# CPUBoard_p2.net
KiCad netlist of a schematic drawn in Altium Designer
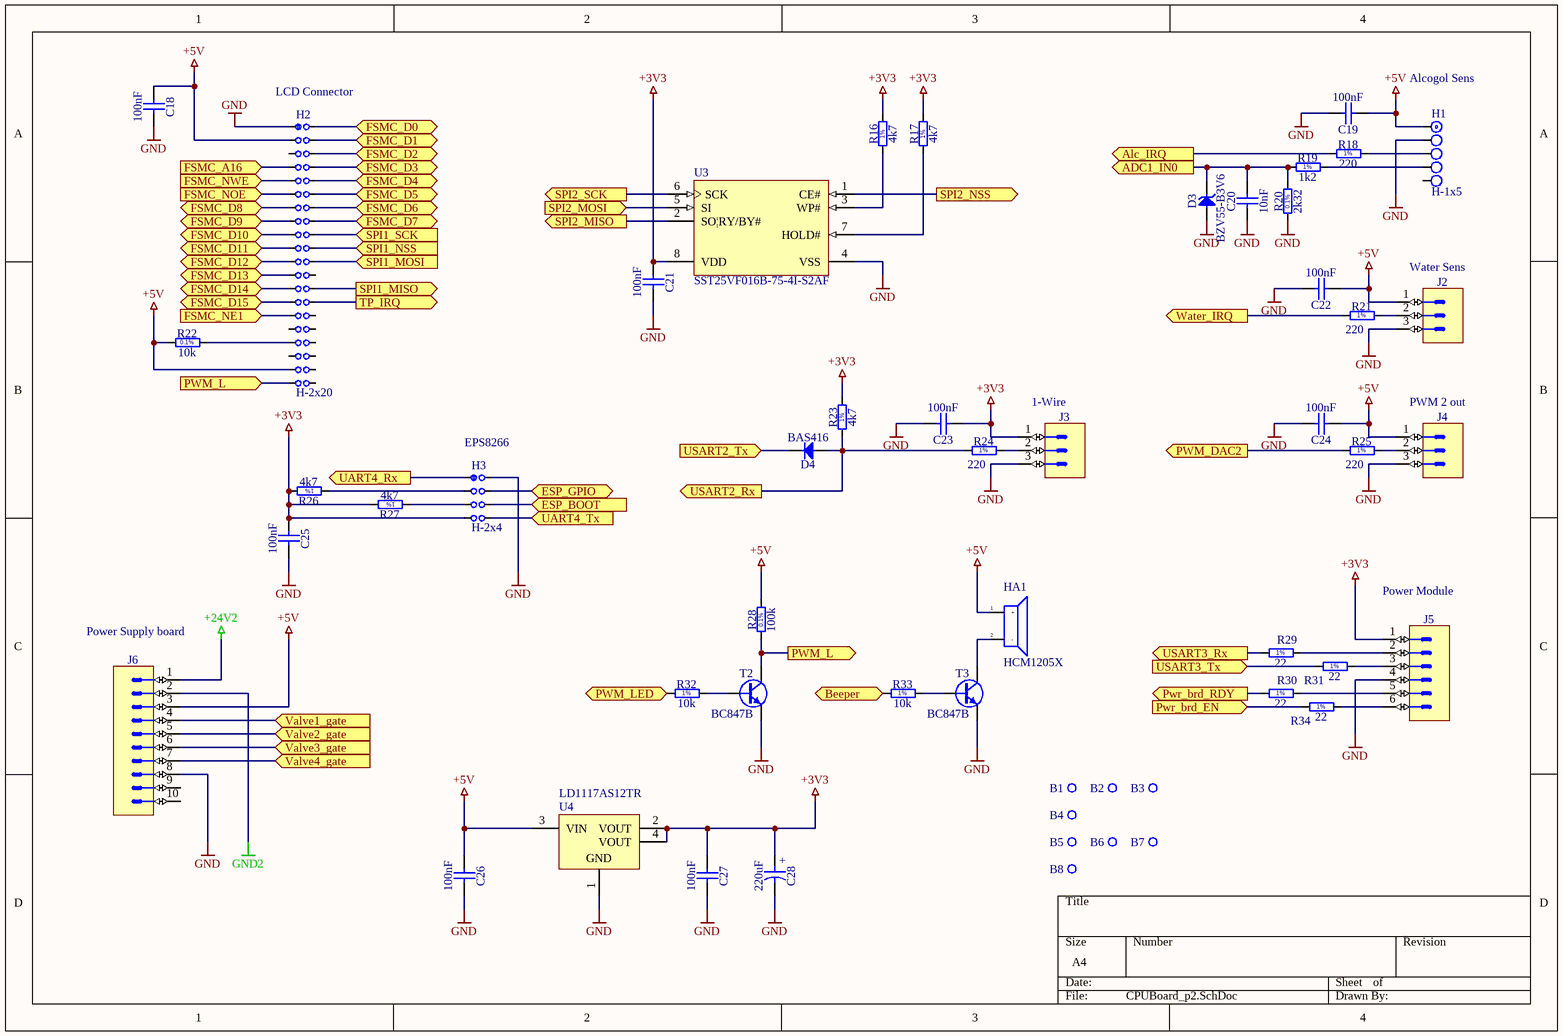
[diagram p0: CPUBoard_p2.SchDoc]

(export (version "E")
  (design (tool "Eeschema 10.0.6"))
  (components
    (comp (ref "B1")
      (value "Plated Hole")
      (footprint "MTG350_650")
      (description "Single Terminal Socket")
      (fields (field (name "PART NUMBER") "PLATED_HOLE3.5_PAD6.5") (field (name "AUTHOR") "CERN DEM JLC"))
      (libsource (lib "Eletro-mechanical") (part "Single Terminal Socket"))
    )
    (comp (ref "B2")
      (value "Plated Hole")
      (footprint "MTG350_650")
      (description "Single Terminal Socket")
      (fields (field (name "PART NUMBER") "PLATED_HOLE3.5_PAD6.5") (field (name "AUTHOR") "CERN DEM JLC"))
      (libsource (lib "Eletro-mechanical") (part "Single Terminal Socket"))
    )
    (comp (ref "B3")
      (value "Plated Hole")
      (footprint "MTG350_650")
      (description "Single Terminal Socket")
      (fields (field (name "PART NUMBER") "PLATED_HOLE3.5_PAD6.5") (field (name "AUTHOR") "CERN DEM JLC"))
      (libsource (lib "Eletro-mechanical") (part "Single Terminal Socket"))
    )
    (comp (ref "B4")
      (value "Plated Hole")
      (footprint "MTG350_650")
      (description "Single Terminal Socket")
      (fields (field (name "PART NUMBER") "PLATED_HOLE3.5_PAD6.5") (field (name "AUTHOR") "CERN DEM JLC"))
      (libsource (lib "Eletro-mechanical") (part "Single Terminal Socket"))
    )
    (comp (ref "B5")
      (value "Plated Hole")
      (footprint "MTG350_650")
      (description "Single Terminal Socket")
      (fields (field (name "PART NUMBER") "PLATED_HOLE3.5_PAD6.5") (field (name "AUTHOR") "CERN DEM JLC"))
      (libsource (lib "Eletro-mechanical") (part "Single Terminal Socket"))
    )
    (comp (ref "B6")
      (value "Plated Hole")
      (footprint "MTG350_650")
      (description "Single Terminal Socket")
      (fields (field (name "PART NUMBER") "PLATED_HOLE3.5_PAD6.5") (field (name "AUTHOR") "CERN DEM JLC"))
      (libsource (lib "Eletro-mechanical") (part "Single Terminal Socket"))
    )
    (comp (ref "B7")
      (value "Plated Hole")
      (footprint "MTG350_650")
      (description "Single Terminal Socket")
      (fields (field (name "PART NUMBER") "PLATED_HOLE3.5_PAD6.5") (field (name "AUTHOR") "CERN DEM JLC"))
      (libsource (lib "Eletro-mechanical") (part "Single Terminal Socket"))
    )
    (comp (ref "B8")
      (value "Plated Hole")
      (footprint "MTG350_650")
      (description "Single Terminal Socket")
      (fields (field (name "PART NUMBER") "PLATED_HOLE3.5_PAD6.5") (field (name "AUTHOR") "CERN DEM JLC"))
      (libsource (lib "Eletro-mechanical") (part "Single Terminal Socket"))
    )
    (comp (ref "C18")
      (value "100nF")
      (footprint "CAPC2012X135N")
      (description "Non-polarised capacitor")
      (fields
        (field (name "PART NUMBER") "CC0805_100NF_50V_10%_X7R")
        (field (name "VOLTAGE") "50V")
        (field (name "AUTHOR") "CERN DEM JLC")
      )
      (libsource (lib "Capacitors") (part "Capacitor - non polarized"))
    )
    (comp (ref "C19")
      (value "100nF")
      (footprint "CAPC2012X135N")
      (description "Non-polarised capacitor")
      (fields
        (field (name "PART NUMBER") "CC0805_100NF_50V_10%_X7R")
        (field (name "VOLTAGE") "50V")
        (field (name "AUTHOR") "CERN DEM JLC")
      )
      (libsource (lib "Capacitors") (part "Capacitor - non polarized"))
    )
    (comp (ref "C20")
      (value "10nF")
      (footprint "CAPC2012X135N")
      (description "Non-polarised capacitor")
      (fields
        (field (name "PART NUMBER") "CC0805_10NF_50V_5%_X7R")
        (field (name "VOLTAGE") "50V")
        (field (name "AUTHOR") "CERN DEM JLC")
      )
      (libsource (lib "Capacitors") (part "Capacitor - non polarized"))
    )
    (comp (ref "C21")
      (value "100nF")
      (footprint "CAPC2012X135N")
      (description "Non-polarised capacitor")
      (fields
        (field (name "PART NUMBER") "CC0805_100NF_50V_10%_X7R")
        (field (name "VOLTAGE") "50V")
        (field (name "AUTHOR") "CERN DEM JLC")
      )
      (libsource (lib "Capacitors") (part "Capacitor - non polarized"))
    )
    (comp (ref "C22")
      (value "100nF")
      (footprint "CAPC2012X135N")
      (description "Non-polarised capacitor")
      (fields
        (field (name "PART NUMBER") "CC0805_100NF_50V_10%_X7R")
        (field (name "VOLTAGE") "50V")
        (field (name "AUTHOR") "CERN DEM JLC")
      )
      (libsource (lib "Capacitors") (part "Capacitor - non polarized"))
    )
    (comp (ref "C23")
      (value "100nF")
      (footprint "CAPC2012X135N")
      (description "Non-polarised capacitor")
      (fields
        (field (name "PART NUMBER") "CC0805_100NF_50V_10%_X7R")
        (field (name "VOLTAGE") "50V")
        (field (name "AUTHOR") "CERN DEM JLC")
      )
      (libsource (lib "Capacitors") (part "Capacitor - non polarized"))
    )
    (comp (ref "C24")
      (value "100nF")
      (footprint "CAPC2012X135N")
      (description "Non-polarised capacitor")
      (fields
        (field (name "PART NUMBER") "CC0805_100NF_50V_10%_X7R")
        (field (name "VOLTAGE") "50V")
        (field (name "AUTHOR") "CERN DEM JLC")
      )
      (libsource (lib "Capacitors") (part "Capacitor - non polarized"))
    )
    (comp (ref "C25")
      (value "100nF")
      (footprint "CAPC2012X135N")
      (description "Non-polarised capacitor")
      (fields
        (field (name "PART NUMBER") "CC0805_100NF_50V_10%_X7R")
        (field (name "VOLTAGE") "50V")
        (field (name "AUTHOR") "CERN DEM JLC")
      )
      (libsource (lib "Capacitors") (part "Capacitor - non polarized"))
    )
    (comp (ref "C26")
      (value "100nF")
      (footprint "CAPC2012X135N")
      (description "Non-polarised capacitor")
      (fields
        (field (name "PART NUMBER") "CC0805_100NF_50V_10%_X7R")
        (field (name "VOLTAGE") "50V")
        (field (name "AUTHOR") "CERN DEM JLC")
      )
      (libsource (lib "Capacitors") (part "Capacitor - non polarized"))
    )
    (comp (ref "C27")
      (value "100nF")
      (footprint "CAPC2012X135N")
      (description "Non-polarised capacitor")
      (fields
        (field (name "PART NUMBER") "CC0805_100NF_50V_10%_X7R")
        (field (name "VOLTAGE") "50V")
        (field (name "AUTHOR") "CERN DEM JLC")
      )
      (libsource (lib "Capacitors") (part "Capacitor - non polarized"))
    )
    (comp (ref "C28")
      (value "220uF")
      (footprint "CAPPR350-850X1300")
      (description "Polarised capacitor")
      (fields
        (field (name "PART NUMBER") "CAER_220UF_25V_20%_RUBYCON_25YXF220M8X11.5")
        (field (name "VOLTAGE") "25V")
        (field (name "AUTHOR") "CERN DEM JLC")
      )
      (libsource (lib "Capacitors") (part "Capacitor - polarized"))
    )
    (comp (ref "D3")
      (value "BZV55-B3V6")
      (footprint "DIOMELF3515N")
      (description "Zener Diode")
      (fields
        (field (name "VOLTAGE") "3V6")
        (field (name "POWER") "500mW")
        (field (name "AUTHOR") "CERN DEM JLC")
      )
      (libsource (lib "ICs And Semiconductors") (part "Diode Zener"))
    )
    (comp (ref "D4")
      (value "BAS416")
      (footprint "SOD2512X110N")
      (description "Diode")
      (fields
        (field (name "VOLTAGE") "75V")
        (field (name "POWER") "200mA")
        (field (name "AUTHOR") "CERN DEM JLC")
      )
      (libsource (lib "ICs And Semiconductors") (part "Diode"))
    )
    (comp (ref "H1") (value "H-1x5") (footprint "J1x5") (libsource (lib "Connektor") (part "H-1x5")))
    (comp (ref "H2") (value "H-2x20") (footprint "J2x20") (libsource (lib "Connektor") (part "H-2x20")))
    (comp (ref "H3") (value "H-2x4") (footprint "J2x4") (libsource (lib "Connektor") (part "H-2x4")))
    (comp (ref "HA1")
      (value "HCM1205X")
      (footprint "HCM1205X")
      (libsource (lib "PowerLib") (part "HCM1205X"))
    )
    (comp (ref "J2")
      (value "KK®")
      (footprint "MOLEX_22-04-1031")
      (description "Connector 3 Male")
      (fields
        (field (name "PART NUMBER") "MOLEX_22-04-1031")
        (field (name "MANUFACTURER") "MOLEX")
        (field (name "AUTHOR") "CERN DEM JLC")
      )
      (libsource (lib "Connectors") (part "Connector 3 Male"))
    )
    (comp (ref "J3")
      (value "KK®")
      (footprint "MOLEX_22-04-1031")
      (description "Connector 3 Male")
      (fields
        (field (name "PART NUMBER") "MOLEX_22-04-1031")
        (field (name "MANUFACTURER") "MOLEX")
        (field (name "AUTHOR") "CERN DEM JLC")
      )
      (libsource (lib "Connectors") (part "Connector 3 Male"))
    )
    (comp (ref "J4")
      (value "KK®")
      (footprint "MOLEX_22-04-1031")
      (description "Connector 3 Male")
      (fields
        (field (name "PART NUMBER") "MOLEX_22-04-1031")
        (field (name "MANUFACTURER") "MOLEX")
        (field (name "AUTHOR") "CERN DEM JLC")
      )
      (libsource (lib "Connectors") (part "Connector 3 Male"))
    )
    (comp (ref "J5")
      (value "KK®")
      (footprint "MOLEX_22-27-2061")
      (description "Connector 6 Male")
      (fields
        (field (name "PART NUMBER") "MOLEX_22-27-2061")
        (field (name "MANUFACTURER") "MOLEX")
        (field (name "AUTHOR") "CERN DEM JMW")
      )
      (libsource (lib "Connectors") (part "Connector 6 Male"))
    )
    (comp (ref "J6")
      (value "C-Grid®")
      (footprint "MOLEX_70246-1004")
      (description "Connector 10 Male")
      (fields
        (field (name "PART NUMBER") "MOLEX_70246-1004")
        (field (name "MANUFACTURER") "MOLEX")
        (field (name "AUTHOR") "CERN DEM JLC")
      )
      (libsource (lib "Connectors") (part "Connector 10 Male"))
    )
    (comp (ref "R16")
      (value "4k7")
      (footprint "RESC2012X60N")
      (description "Resistor - 1%")
      (fields
        (field (name "PART NUMBER") "R0805_4K7_1%_0.125W_100PPM")
        (field (name "POWER") "0.125W")
        (field (name "AUTHOR") "CERN DEM JLC")
      )
      (libsource (lib "Resistors") (part "Resistor - 1%"))
    )
    (comp (ref "R17")
      (value "4k7")
      (footprint "RESC2012X60N")
      (description "Resistor - 1%")
      (fields
        (field (name "PART NUMBER") "R0805_4K7_1%_0.125W_100PPM")
        (field (name "POWER") "0.125W")
        (field (name "AUTHOR") "CERN DEM JLC")
      )
      (libsource (lib "Resistors") (part "Resistor - 1%"))
    )
    (comp (ref "R18")
      (value "220")
      (footprint "RESC2012X60N")
      (description "Resistor - 1%")
      (fields
        (field (name "PART NUMBER") "R0805_220R_1%_0.125W_100PPM")
        (field (name "POWER") "0.125W")
        (field (name "AUTHOR") "CERN DEM JLC")
      )
      (libsource (lib "Resistors") (part "Resistor - 1%"))
    )
    (comp (ref "R19")
      (value "1k2")
      (footprint "RESC2012X60N")
      (description "Resistor - 1%")
      (fields
        (field (name "PART NUMBER") "R0805_1K2_1%_0.125W_100PPM")
        (field (name "POWER") "0.125W")
        (field (name "AUTHOR") "CERN DEM JLC")
      )
      (libsource (lib "Resistors") (part "Resistor - 1%"))
    )
    (comp (ref "R20")
      (value "2k32")
      (footprint "RESC2012X60N")
      (description "Resistor - 0.1%")
      (fields
        (field (name "PART NUMBER") "R0805_2K32_0.1%_0.1W_10PPM")
        (field (name "POWER") "0.1W")
        (field (name "AUTHOR") "CERN DEM JLC")
      )
      (libsource (lib "Resistors") (part "Resistor - 0.1%"))
    )
    (comp (ref "R21")
      (value "220")
      (footprint "RESC2012X60N")
      (description "Resistor - 1%")
      (fields
        (field (name "PART NUMBER") "R0805_220R_1%_0.125W_100PPM")
        (field (name "POWER") "0.125W")
        (field (name "AUTHOR") "CERN DEM JLC")
      )
      (libsource (lib "Resistors") (part "Resistor - 1%"))
    )
    (comp (ref "R22")
      (value "10k")
      (footprint "RESC2012X60N")
      (description "Resistor - 0.1%")
      (fields
        (field (name "PART NUMBER") "R0805_10K_0.1%_0.1W_10PPM")
        (field (name "POWER") "0.1W")
        (field (name "AUTHOR") "CERN DEM JLC")
      )
      (libsource (lib "Resistors") (part "Resistor - 0.1%"))
    )
    (comp (ref "R23")
      (value "4k7")
      (footprint "RESC2012X60N")
      (description "Resistor - 1%")
      (fields
        (field (name "PART NUMBER") "R0805_4K7_1%_0.125W_100PPM")
        (field (name "POWER") "0.125W")
        (field (name "AUTHOR") "CERN DEM JLC")
      )
      (libsource (lib "Resistors") (part "Resistor - 1%"))
    )
    (comp (ref "R24")
      (value "220")
      (footprint "RESC2012X60N")
      (description "Resistor - 1%")
      (fields
        (field (name "PART NUMBER") "R0805_220R_1%_0.125W_100PPM")
        (field (name "POWER") "0.125W")
        (field (name "AUTHOR") "CERN DEM JLC")
      )
      (libsource (lib "Resistors") (part "Resistor - 1%"))
    )
    (comp (ref "R25")
      (value "220")
      (footprint "RESC2012X60N")
      (description "Resistor - 1%")
      (fields
        (field (name "PART NUMBER") "R0805_220R_1%_0.125W_100PPM")
        (field (name "POWER") "0.125W")
        (field (name "AUTHOR") "CERN DEM JLC")
      )
      (libsource (lib "Resistors") (part "Resistor - 1%"))
    )
    (comp (ref "R26")
      (value "4k7")
      (footprint "RESC2012X60N")
      (description "Resistor - 1%")
      (fields
        (field (name "PART NUMBER") "R0805_4K7_1%_0.125W_100PPM")
        (field (name "POWER") "0.125W")
        (field (name "AUTHOR") "CERN DEM JLC")
      )
      (libsource (lib "Resistors") (part "Resistor - 1%"))
    )
    (comp (ref "R27")
      (value "4k7")
      (footprint "RESC2012X60N")
      (description "Resistor - 1%")
      (fields
        (field (name "PART NUMBER") "R0805_4K7_1%_0.125W_100PPM")
        (field (name "POWER") "0.125W")
        (field (name "AUTHOR") "CERN DEM JLC")
      )
      (libsource (lib "Resistors") (part "Resistor - 1%"))
    )
    (comp (ref "R28")
      (value "100k")
      (footprint "RESC2012X60N")
      (description "Resistor - 0.1%")
      (fields
        (field (name "PART NUMBER") "R0805_100K_0.1%_0.1W_10PPM")
        (field (name "POWER") "0.1W")
        (field (name "AUTHOR") "CERN DEM JLC")
      )
      (libsource (lib "Resistors") (part "Resistor - 0.1%"))
    )
    (comp (ref "R29")
      (value "22")
      (footprint "RESC2012X60N")
      (description "Resistor - 1%")
      (fields
        (field (name "PART NUMBER") "R0805_22R_1%_0.125W_100PPM")
        (field (name "POWER") "0.125W")
        (field (name "AUTHOR") "CERN DEM JLC")
      )
      (libsource (lib "Resistors") (part "Resistor - 1%"))
    )
    (comp (ref "R30")
      (value "22")
      (footprint "RESC2012X60N")
      (description "Resistor - 1%")
      (fields
        (field (name "PART NUMBER") "R0805_22R_1%_0.125W_100PPM")
        (field (name "POWER") "0.125W")
        (field (name "AUTHOR") "CERN DEM JLC")
      )
      (libsource (lib "Resistors") (part "Resistor - 1%"))
    )
    (comp (ref "R31")
      (value "22")
      (footprint "RESC2012X60N")
      (description "Resistor - 1%")
      (fields
        (field (name "PART NUMBER") "R0805_22R_1%_0.125W_100PPM")
        (field (name "POWER") "0.125W")
        (field (name "AUTHOR") "CERN DEM JLC")
      )
      (libsource (lib "Resistors") (part "Resistor - 1%"))
    )
    (comp (ref "R32")
      (value "10k")
      (footprint "RESC2012X60N")
      (description "Resistor - 1%")
      (fields
        (field (name "PART NUMBER") "R0805_10K_1%_0.125W_100PPM")
        (field (name "POWER") "0.125W")
        (field (name "AUTHOR") "CERN DEM JLC")
      )
      (libsource (lib "Resistors") (part "Resistor - 1%"))
    )
    (comp (ref "R33")
      (value "10k")
      (footprint "RESC2012X60N")
      (description "Resistor - 1%")
      (fields
        (field (name "PART NUMBER") "R0805_10K_1%_0.125W_100PPM")
        (field (name "POWER") "0.125W")
        (field (name "AUTHOR") "CERN DEM JLC")
      )
      (libsource (lib "Resistors") (part "Resistor - 1%"))
    )
    (comp (ref "R34")
      (value "22")
      (footprint "RESC2012X60N")
      (description "Resistor - 1%")
      (fields
        (field (name "PART NUMBER") "R0805_22R_1%_0.125W_100PPM")
        (field (name "POWER") "0.125W")
        (field (name "AUTHOR") "CERN DEM JLC")
      )
      (libsource (lib "Resistors") (part "Resistor - 1%"))
    )
    (comp (ref "T2")
      (value "BC847B")
      (footprint "SOT95P230X110-3N")
      (description "NPN Transistor")
      (fields (field (name "MANUFACTURER") "NXP SEMICONDUCTORS") (field (name "AUTHOR") "CERN DEM JLC"))
      (libsource (lib "ICs And Semiconductors") (part "NPN B1 E2 C3"))
    )
    (comp (ref "T3")
      (value "BC847B")
      (footprint "SOT95P230X110-3N")
      (description "NPN Transistor")
      (fields (field (name "MANUFACTURER") "NXP SEMICONDUCTORS") (field (name "AUTHOR") "CERN DEM JLC"))
      (libsource (lib "ICs And Semiconductors") (part "NPN B1 E2 C3"))
    )
    (comp (ref "U3")
      (value "SST25VF016B-75-4I-S2AF")
      (footprint "MCHP-SOIC-S2A8_N")
      (description "16 Mbit SPI Serial Flash, 2.7 to 3.6 V, 80 MHz, -40 to 85 degC, 8-pin SOIC (S2A8), Tube")
      (fields (field (name "MANUFACTURER") "Microchip"))
      (libsource (lib "Microchip SST Flash") (part "SST25VF016B-75-4I-S2AF"))
    )
    (comp (ref "U4")
      (value "LD1117AS12TR")
      (footprint "SOT-223_N")
      (description "1A, Low Drop Positive Voltage Regulator, 1.2V, 4-Pin SOT-223, Tape and Reel")
      (libsource (lib "STMicroelectronics Power Management Linear Regulator") (part "LD1117AS12TR"))
    )
  )
  (nets
    (net (code "1") (name "+3V3") (class "Default")
      (node (ref "C21") (pin "1") (pinfunction "1_1") (pintype "passive"))
      (node (ref "C23") (pin "1") (pinfunction "1_1") (pintype "passive"))
      (node (ref "C25") (pin "1") (pinfunction "1_1") (pintype "passive"))
      (node (ref "C27") (pin "1") (pinfunction "1_1") (pintype "passive"))
      (node (ref "C28") (pin "1") (pinfunction "1_1") (pintype "passive"))
      (node (ref "H3") (pin "7") (pinfunction "7_7") (pintype "passive"))
      (node (ref "J3") (pin "1") (pinfunction "1_1") (pintype "bidirectional"))
      (node (ref "J5") (pin "1") (pinfunction "1_1") (pintype "bidirectional"))
      (node (ref "R16") (pin "2") (pinfunction "2_2") (pintype "passive"))
      (node (ref "R17") (pin "2") (pinfunction "2_2") (pintype "passive"))
      (node (ref "R23") (pin "2") (pinfunction "2_2") (pintype "passive"))
      (node (ref "R26") (pin "2") (pinfunction "2_2") (pintype "passive"))
      (node (ref "R27") (pin "2") (pinfunction "2_2") (pintype "passive"))
      (node (ref "U3") (pin "8") (pinfunction "VDD_8") (pintype "power_in"))
      (node (ref "U4") (pin "2") (pinfunction "VOUT_2") (pintype "power_in"))
      (node (ref "U4") (pin "4") (pinfunction "VOUT_4") (pintype "power_in"))
    )
    (net (code "2") (name "+5V") (class "Default")
      (node (ref "C18") (pin "1") (pinfunction "1_1") (pintype "passive"))
      (node (ref "C19") (pin "1") (pinfunction "1_1") (pintype "passive"))
      (node (ref "C22") (pin "1") (pinfunction "1_1") (pintype "passive"))
      (node (ref "C24") (pin "1") (pinfunction "1_1") (pintype "passive"))
      (node (ref "C26") (pin "1") (pinfunction "1_1") (pintype "passive"))
      (node (ref "H1") (pin "1") (pinfunction "1_1") (pintype "passive"))
      (node (ref "H2") (pin "3") (pinfunction "3_3") (pintype "passive"))
      (node (ref "H2") (pin "37") (pinfunction "37_37") (pintype "passive"))
      (node (ref "HA1") (pin "1") (pinfunction "+_1") (pintype "passive"))
      (node (ref "J2") (pin "1") (pinfunction "1_1") (pintype "bidirectional"))
      (node (ref "J4") (pin "1") (pinfunction "1_1") (pintype "bidirectional"))
      (node (ref "J6") (pin "3") (pinfunction "3_3") (pintype "bidirectional"))
      (node (ref "R22") (pin "1") (pinfunction "1_1") (pintype "passive"))
      (node (ref "R28") (pin "2") (pinfunction "2_2") (pintype "passive"))
      (node (ref "U4") (pin "3") (pinfunction "VIN_3") (pintype "power_in"))
    )
    (net (code "3") (name "+24V2") (class "Default")
      (node (ref "J6") (pin "1") (pinfunction "1_1") (pintype "bidirectional"))
    )
    (net (code "4") (name "/ADC1_IN0") (class "Default")
      (node (ref "C20") (pin "2") (pinfunction "2_2") (pintype "passive"))
      (node (ref "D3") (pin "1") (pinfunction "C_1") (pintype "passive"))
      (node (ref "R19") (pin "1") (pinfunction "1_1") (pintype "passive"))
      (node (ref "R20") (pin "2") (pinfunction "2_2") (pintype "passive"))
    )
    (net (code "5") (name "/Alc_IRQ") (class "Default")
      (node (ref "R18") (pin "1") (pinfunction "1_1") (pintype "passive"))
    )
    (net (code "6") (name "/Beeper") (class "Default")
      (node (ref "R33") (pin "1") (pinfunction "1_1") (pintype "passive"))
    )
    (net (code "7") (name "/ESP_BOOT") (class "Default")
      (node (ref "H3") (pin "6") (pinfunction "6_6") (pintype "passive"))
    )
    (net (code "8") (name "/ESP_GPIO") (class "Default")
      (node (ref "H3") (pin "4") (pinfunction "4_4") (pintype "passive"))
    )
    (net (code "9") (name "/FSMC_A16") (class "Default")
      (node (ref "H2") (pin "7") (pinfunction "7_7") (pintype "passive"))
    )
    (net (code "10") (name "/FSMC_D0") (class "Default")
      (node (ref "H2") (pin "2") (pinfunction "2_2") (pintype "passive"))
    )
    (net (code "11") (name "/FSMC_D1") (class "Default")
      (node (ref "H2") (pin "4") (pinfunction "4_4") (pintype "passive"))
    )
    (net (code "12") (name "/FSMC_D2") (class "Default")
      (node (ref "H2") (pin "6") (pinfunction "6_6") (pintype "passive"))
    )
    (net (code "13") (name "/FSMC_D3") (class "Default")
      (node (ref "H2") (pin "8") (pinfunction "8_8") (pintype "passive"))
    )
    (net (code "14") (name "/FSMC_D4") (class "Default")
      (node (ref "H2") (pin "10") (pinfunction "10_10") (pintype "passive"))
    )
    (net (code "15") (name "/FSMC_D5") (class "Default")
      (node (ref "H2") (pin "12") (pinfunction "12_12") (pintype "passive"))
    )
    (net (code "16") (name "/FSMC_D6") (class "Default")
      (node (ref "H2") (pin "14") (pinfunction "14_14") (pintype "passive"))
    )
    (net (code "17") (name "/FSMC_D7") (class "Default")
      (node (ref "H2") (pin "16") (pinfunction "16_16") (pintype "passive"))
    )
    (net (code "18") (name "/FSMC_D8") (class "Default")
      (node (ref "H2") (pin "13") (pinfunction "13_13") (pintype "passive"))
    )
    (net (code "19") (name "/FSMC_D9") (class "Default")
      (node (ref "H2") (pin "15") (pinfunction "15_15") (pintype "passive"))
    )
    (net (code "20") (name "/FSMC_D10") (class "Default")
      (node (ref "H2") (pin "17") (pinfunction "17_17") (pintype "passive"))
    )
    (net (code "21") (name "/FSMC_D11") (class "Default")
      (node (ref "H2") (pin "19") (pinfunction "19_19") (pintype "passive"))
    )
    (net (code "22") (name "/FSMC_D12") (class "Default")
      (node (ref "H2") (pin "21") (pinfunction "21_21") (pintype "passive"))
    )
    (net (code "23") (name "/FSMC_D13") (class "Default")
      (node (ref "H2") (pin "23") (pinfunction "23_23") (pintype "passive"))
    )
    (net (code "24") (name "/FSMC_D14") (class "Default")
      (node (ref "H2") (pin "25") (pinfunction "25_25") (pintype "passive"))
    )
    (net (code "25") (name "/FSMC_D15") (class "Default")
      (node (ref "H2") (pin "27") (pinfunction "27_27") (pintype "passive"))
    )
    (net (code "26") (name "/FSMC_NE1") (class "Default")
      (node (ref "H2") (pin "29") (pinfunction "29_29") (pintype "passive"))
    )
    (net (code "27") (name "/FSMC_NOE") (class "Default")
      (node (ref "H2") (pin "11") (pinfunction "11_11") (pintype "passive"))
    )
    (net (code "28") (name "/FSMC_NWE") (class "Default")
      (node (ref "H2") (pin "9") (pinfunction "9_9") (pintype "passive"))
    )
    (net (code "29") (name "/PWM_DAC2") (class "Default")
      (node (ref "R25") (pin "1") (pinfunction "1_1") (pintype "passive"))
    )
    (net (code "30") (name "/PWM_L") (class "Default")
      (node (ref "H2") (pin "39") (pinfunction "39_39") (pintype "passive"))
      (node (ref "R28") (pin "1") (pinfunction "1_1") (pintype "passive"))
      (node (ref "T2") (pin "3") (pinfunction "C_3") (pintype "passive"))
    )
    (net (code "31") (name "/PWM_LED") (class "Default")
      (node (ref "R32") (pin "1") (pinfunction "1_1") (pintype "passive"))
    )
    (net (code "32") (name "/Pwr_brd_EN") (class "Default")
      (node (ref "R34") (pin "1") (pinfunction "1_1") (pintype "passive"))
    )
    (net (code "33") (name "/Pwr_brd_RDY") (class "Default")
      (node (ref "R30") (pin "1") (pinfunction "1_1") (pintype "passive"))
    )
    (net (code "34") (name "/SPI1_MISO") (class "Default")
      (node (ref "H2") (pin "26") (pinfunction "26_26") (pintype "passive"))
    )
    (net (code "35") (name "/SPI1_MOSI") (class "Default")
      (node (ref "H2") (pin "22") (pinfunction "22_22") (pintype "passive"))
    )
    (net (code "36") (name "/SPI1_NSS") (class "Default")
      (node (ref "H2") (pin "20") (pinfunction "20_20") (pintype "passive"))
    )
    (net (code "37") (name "/SPI1_SCK") (class "Default")
      (node (ref "H2") (pin "18") (pinfunction "18_18") (pintype "passive"))
    )
    (net (code "38") (name "/SPI2_MISO") (class "Default")
      (node (ref "U3") (pin "2") (pinfunction "SO¦RY/BY#_2") (pintype "tri_state"))
    )
    (net (code "39") (name "/SPI2_MOSI") (class "Default")
      (node (ref "U3") (pin "5") (pinfunction "SI_5") (pintype "input"))
    )
    (net (code "40") (name "/SPI2_NSS") (class "Default")
      (node (ref "U3") (pin "1") (pinfunction "CE#_1") (pintype "input"))
    )
    (net (code "41") (name "/SPI2_SCK") (class "Default")
      (node (ref "U3") (pin "6") (pinfunction "SCK_6") (pintype "input"))
    )
    (net (code "42") (name "/TP_IRQ") (class "Default")
      (node (ref "H2") (pin "28") (pinfunction "28_28") (pintype "passive"))
    )
    (net (code "43") (name "/UART4_Rx") (class "Default")
      (node (ref "H3") (pin "1") (pinfunction "1_1") (pintype "passive"))
    )
    (net (code "44") (name "/UART4_Tx") (class "Default")
      (node (ref "H3") (pin "8") (pinfunction "8_8") (pintype "passive"))
    )
    (net (code "45") (name "/USART2_Rx") (class "Default")
      (node (ref "D4") (pin "2") (pinfunction "A_2") (pintype "passive"))
      (node (ref "R23") (pin "1") (pinfunction "1_1") (pintype "passive"))
      (node (ref "R24") (pin "1") (pinfunction "1_1") (pintype "passive"))
    )
    (net (code "46") (name "/USART2_Tx") (class "Default")
      (node (ref "D4") (pin "1") (pinfunction "C_1") (pintype "passive"))
    )
    (net (code "47") (name "/USART3_Rx") (class "Default")
      (node (ref "R29") (pin "1") (pinfunction "1_1") (pintype "passive"))
    )
    (net (code "48") (name "/USART3_Tx") (class "Default")
      (node (ref "R31") (pin "1") (pinfunction "1_1") (pintype "passive"))
    )
    (net (code "49") (name "/Valve1_gate") (class "Default")
      (node (ref "J6") (pin "4") (pinfunction "4_4") (pintype "bidirectional"))
    )
    (net (code "50") (name "/Valve2_gate") (class "Default")
      (node (ref "J6") (pin "5") (pinfunction "5_5") (pintype "bidirectional"))
    )
    (net (code "51") (name "/Valve3_gate") (class "Default")
      (node (ref "J6") (pin "6") (pinfunction "6_6") (pintype "bidirectional"))
    )
    (net (code "52") (name "/Valve4_gate") (class "Default")
      (node (ref "J6") (pin "7") (pinfunction "7_7") (pintype "bidirectional"))
    )
    (net (code "53") (name "/Water_IRQ") (class "Default")
      (node (ref "R21") (pin "1") (pinfunction "1_1") (pintype "passive"))
    )
    (net (code "54") (name "GND") (class "Default")
      (node (ref "C18") (pin "2") (pinfunction "2_2") (pintype "passive"))
      (node (ref "C19") (pin "2") (pinfunction "2_2") (pintype "passive"))
      (node (ref "C20") (pin "1") (pinfunction "1_1") (pintype "passive"))
      (node (ref "C21") (pin "2") (pinfunction "2_2") (pintype "passive"))
      (node (ref "C22") (pin "2") (pinfunction "2_2") (pintype "passive"))
      (node (ref "C23") (pin "2") (pinfunction "2_2") (pintype "passive"))
      (node (ref "C24") (pin "2") (pinfunction "2_2") (pintype "passive"))
      (node (ref "C25") (pin "2") (pinfunction "2_2") (pintype "passive"))
      (node (ref "C26") (pin "2") (pinfunction "2_2") (pintype "passive"))
      (node (ref "C27") (pin "2") (pinfunction "2_2") (pintype "passive"))
      (node (ref "C28") (pin "2") (pinfunction "2_2") (pintype "passive"))
      (node (ref "D3") (pin "2") (pinfunction "A_2") (pintype "passive"))
      (node (ref "H1") (pin "2") (pinfunction "2_2") (pintype "passive"))
      (node (ref "H2") (pin "1") (pinfunction "1_1") (pintype "passive"))
      (node (ref "H3") (pin "2") (pinfunction "2_2") (pintype "passive"))
      (node (ref "J2") (pin "3") (pinfunction "3_3") (pintype "bidirectional"))
      (node (ref "J3") (pin "3") (pinfunction "3_3") (pintype "bidirectional"))
      (node (ref "J4") (pin "3") (pinfunction "3_3") (pintype "bidirectional"))
      (node (ref "J5") (pin "4") (pinfunction "4_4") (pintype "bidirectional"))
      (node (ref "J6") (pin "8") (pinfunction "8_8") (pintype "bidirectional"))
      (node (ref "R20") (pin "1") (pinfunction "1_1") (pintype "passive"))
      (node (ref "T2") (pin "2") (pinfunction "E_2") (pintype "passive"))
      (node (ref "T3") (pin "2") (pinfunction "E_2") (pintype "passive"))
      (node (ref "U3") (pin "4") (pinfunction "VSS_4") (pintype "power_in"))
      (node (ref "U4") (pin "1") (pinfunction "GND_1") (pintype "power_in"))
    )
    (net (code "55") (name "GND2") (class "Default")
      (node (ref "J6") (pin "2") (pinfunction "2_2") (pintype "bidirectional"))
    )
    (net (code "56") (name "Net-(H1-Pad3)") (class "Default")
      (node (ref "H1") (pin "3") (pinfunction "3_3") (pintype "passive"))
      (node (ref "R18") (pin "2") (pinfunction "2_2") (pintype "passive"))
    )
    (net (code "57") (name "Net-(H1-Pad4)") (class "Default")
      (node (ref "H1") (pin "4") (pinfunction "4_4") (pintype "passive"))
      (node (ref "R19") (pin "2") (pinfunction "2_2") (pintype "passive"))
    )
    (net (code "58") (name "Net-(H2-Pad33)") (class "Default")
      (node (ref "H2") (pin "33") (pinfunction "33_33") (pintype "passive"))
      (node (ref "R22") (pin "2") (pinfunction "2_2") (pintype "passive"))
    )
    (net (code "59") (name "Net-(H3-Pad3)") (class "Default")
      (node (ref "H3") (pin "3") (pinfunction "3_3") (pintype "passive"))
      (node (ref "R26") (pin "1") (pinfunction "1_1") (pintype "passive"))
    )
    (net (code "60") (name "Net-(H3-Pad5)") (class "Default")
      (node (ref "H3") (pin "5") (pinfunction "5_5") (pintype "passive"))
      (node (ref "R27") (pin "1") (pinfunction "1_1") (pintype "passive"))
    )
    (net (code "61") (name "Net-(HA1--)") (class "Default")
      (node (ref "HA1") (pin "2") (pinfunction "-_2") (pintype "passive"))
      (node (ref "T3") (pin "3") (pinfunction "C_3") (pintype "passive"))
    )
    (net (code "62") (name "Net-(J2-Pad2)") (class "Default")
      (node (ref "J2") (pin "2") (pinfunction "2_2") (pintype "bidirectional"))
      (node (ref "R21") (pin "2") (pinfunction "2_2") (pintype "passive"))
    )
    (net (code "63") (name "Net-(J3-Pad2)") (class "Default")
      (node (ref "J3") (pin "2") (pinfunction "2_2") (pintype "bidirectional"))
      (node (ref "R24") (pin "2") (pinfunction "2_2") (pintype "passive"))
    )
    (net (code "64") (name "Net-(J4-Pad2)") (class "Default")
      (node (ref "J4") (pin "2") (pinfunction "2_2") (pintype "bidirectional"))
      (node (ref "R25") (pin "2") (pinfunction "2_2") (pintype "passive"))
    )
    (net (code "65") (name "Net-(J5-Pad2)") (class "Default")
      (node (ref "J5") (pin "2") (pinfunction "2_2") (pintype "bidirectional"))
      (node (ref "R29") (pin "2") (pinfunction "2_2") (pintype "passive"))
    )
    (net (code "66") (name "Net-(J5-Pad3)") (class "Default")
      (node (ref "J5") (pin "3") (pinfunction "3_3") (pintype "bidirectional"))
      (node (ref "R31") (pin "2") (pinfunction "2_2") (pintype "passive"))
    )
    (net (code "67") (name "Net-(J5-Pad5)") (class "Default")
      (node (ref "J5") (pin "5") (pinfunction "5_5") (pintype "bidirectional"))
      (node (ref "R30") (pin "2") (pinfunction "2_2") (pintype "passive"))
    )
    (net (code "68") (name "Net-(J5-Pad6)") (class "Default")
      (node (ref "J5") (pin "6") (pinfunction "6_6") (pintype "bidirectional"))
      (node (ref "R34") (pin "2") (pinfunction "2_2") (pintype "passive"))
    )
    (net (code "69") (name "Net-(T2-B)") (class "Default")
      (node (ref "R32") (pin "2") (pinfunction "2_2") (pintype "passive"))
      (node (ref "T2") (pin "1") (pinfunction "B_1") (pintype "passive"))
    )
    (net (code "70") (name "Net-(T3-B)") (class "Default")
      (node (ref "R33") (pin "2") (pinfunction "2_2") (pintype "passive"))
      (node (ref "T3") (pin "1") (pinfunction "B_1") (pintype "passive"))
    )
    (net (code "71") (name "Net-(U3-HOLD#)") (class "Default")
      (node (ref "R17") (pin "1") (pinfunction "1_1") (pintype "passive"))
      (node (ref "U3") (pin "7") (pinfunction "HOLD#_7") (pintype "input"))
    )
    (net (code "72") (name "Net-(U3-WP#)") (class "Default")
      (node (ref "R16") (pin "1") (pinfunction "1_1") (pintype "passive"))
      (node (ref "U3") (pin "3") (pinfunction "WP#_3") (pintype "input"))
    )
    (net (code "73") (name "unconnected-(B1-Pad1)") (class "Default")
      (node (ref "B1") (pin "1") (pinfunction "1_1") (pintype "bidirectional"))
    )
    (net (code "74") (name "unconnected-(B2-Pad1)") (class "Default")
      (node (ref "B2") (pin "1") (pinfunction "1_1") (pintype "bidirectional"))
    )
    (net (code "75") (name "unconnected-(B3-Pad1)") (class "Default")
      (node (ref "B3") (pin "1") (pinfunction "1_1") (pintype "bidirectional"))
    )
    (net (code "76") (name "unconnected-(B4-Pad1)") (class "Default")
      (node (ref "B4") (pin "1") (pinfunction "1_1") (pintype "bidirectional"))
    )
    (net (code "77") (name "unconnected-(B5-Pad1)") (class "Default")
      (node (ref "B5") (pin "1") (pinfunction "1_1") (pintype "bidirectional"))
    )
    (net (code "78") (name "unconnected-(B6-Pad1)") (class "Default")
      (node (ref "B6") (pin "1") (pinfunction "1_1") (pintype "bidirectional"))
    )
    (net (code "79") (name "unconnected-(B7-Pad1)") (class "Default")
      (node (ref "B7") (pin "1") (pinfunction "1_1") (pintype "bidirectional"))
    )
    (net (code "80") (name "unconnected-(B8-Pad1)") (class "Default")
      (node (ref "B8") (pin "1") (pinfunction "1_1") (pintype "bidirectional"))
    )
    (net (code "81") (name "unconnected-(H1-Pad5)") (class "Default")
      (node (ref "H1") (pin "5") (pinfunction "5_5") (pintype "passive"))
    )
    (net (code "82") (name "unconnected-(H2-Pad5)") (class "Default")
      (node (ref "H2") (pin "5") (pinfunction "5_5") (pintype "passive"))
    )
    (net (code "83") (name "unconnected-(H2-Pad24)") (class "Default")
      (node (ref "H2") (pin "24") (pinfunction "24_24") (pintype "passive"))
    )
    (net (code "84") (name "unconnected-(H2-Pad30)") (class "Default")
      (node (ref "H2") (pin "30") (pinfunction "30_30") (pintype "passive"))
    )
    (net (code "85") (name "unconnected-(H2-Pad31)") (class "Default")
      (node (ref "H2") (pin "31") (pinfunction "31_31") (pintype "passive"))
    )
    (net (code "86") (name "unconnected-(H2-Pad32)") (class "Default")
      (node (ref "H2") (pin "32") (pinfunction "32_32") (pintype "passive"))
    )
    (net (code "87") (name "unconnected-(H2-Pad34)") (class "Default")
      (node (ref "H2") (pin "34") (pinfunction "34_34") (pintype "passive"))
    )
    (net (code "88") (name "unconnected-(H2-Pad35)") (class "Default")
      (node (ref "H2") (pin "35") (pinfunction "35_35") (pintype "passive"))
    )
    (net (code "89") (name "unconnected-(H2-Pad36)") (class "Default")
      (node (ref "H2") (pin "36") (pinfunction "36_36") (pintype "passive"))
    )
    (net (code "90") (name "unconnected-(H2-Pad38)") (class "Default")
      (node (ref "H2") (pin "38") (pinfunction "38_38") (pintype "passive"))
    )
    (net (code "91") (name "unconnected-(H2-Pad40)") (class "Default")
      (node (ref "H2") (pin "40") (pinfunction "40_40") (pintype "passive"))
    )
    (net (code "92") (name "unconnected-(J6-Pad9)") (class "Default")
      (node (ref "J6") (pin "9") (pinfunction "9_9") (pintype "bidirectional"))
    )
    (net (code "93") (name "unconnected-(J6-Pad10)") (class "Default")
      (node (ref "J6") (pin "10") (pinfunction "10_10") (pintype "bidirectional"))
    )
  )
)
